# Lab_6.net
KiCad netlist of a schematic drawn in EAGLE
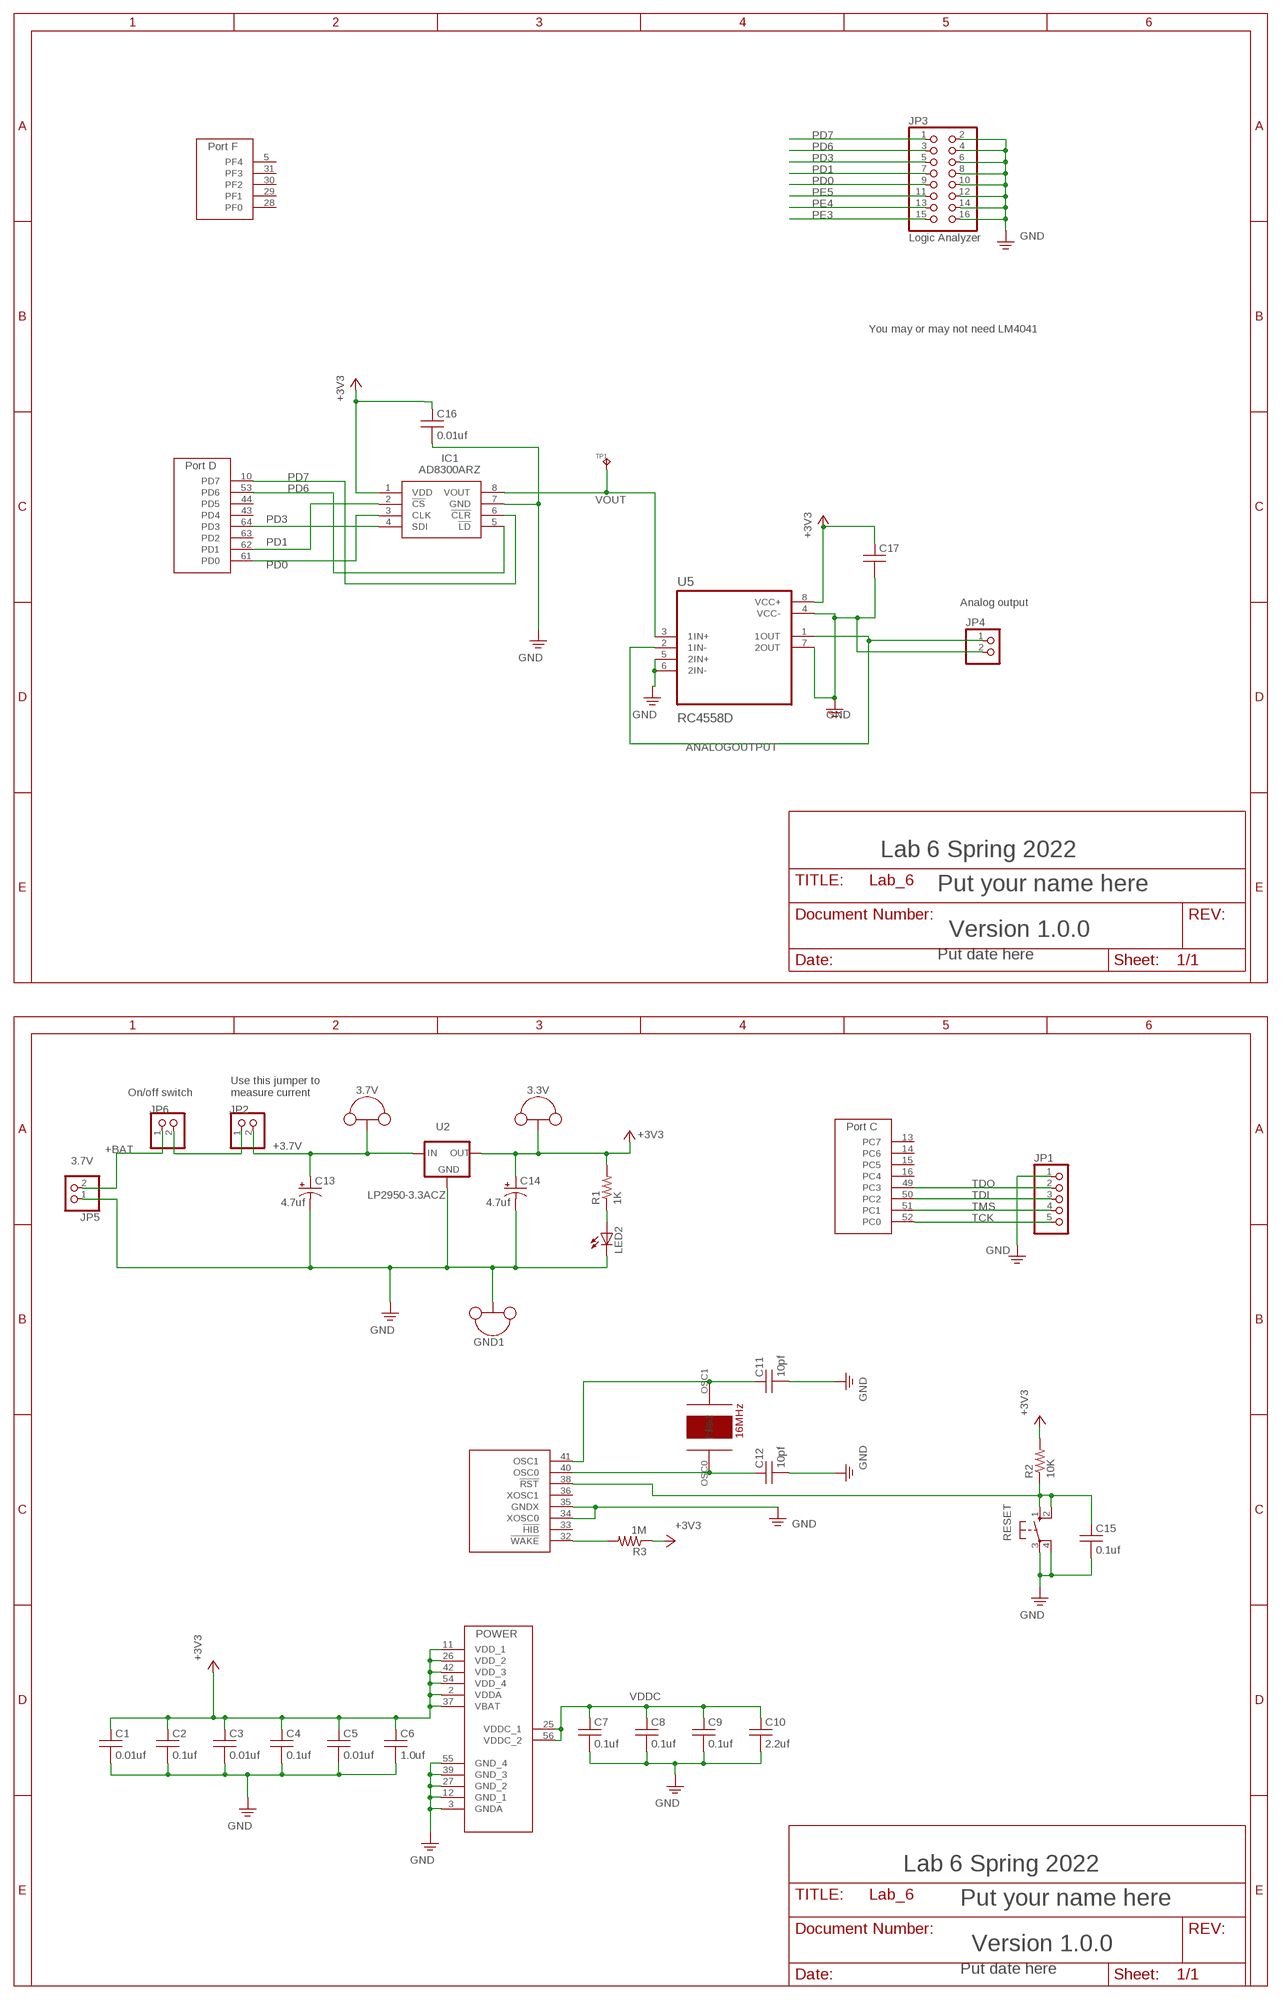
[diagram p0: schematic, sheet 1, part 1 of 2]
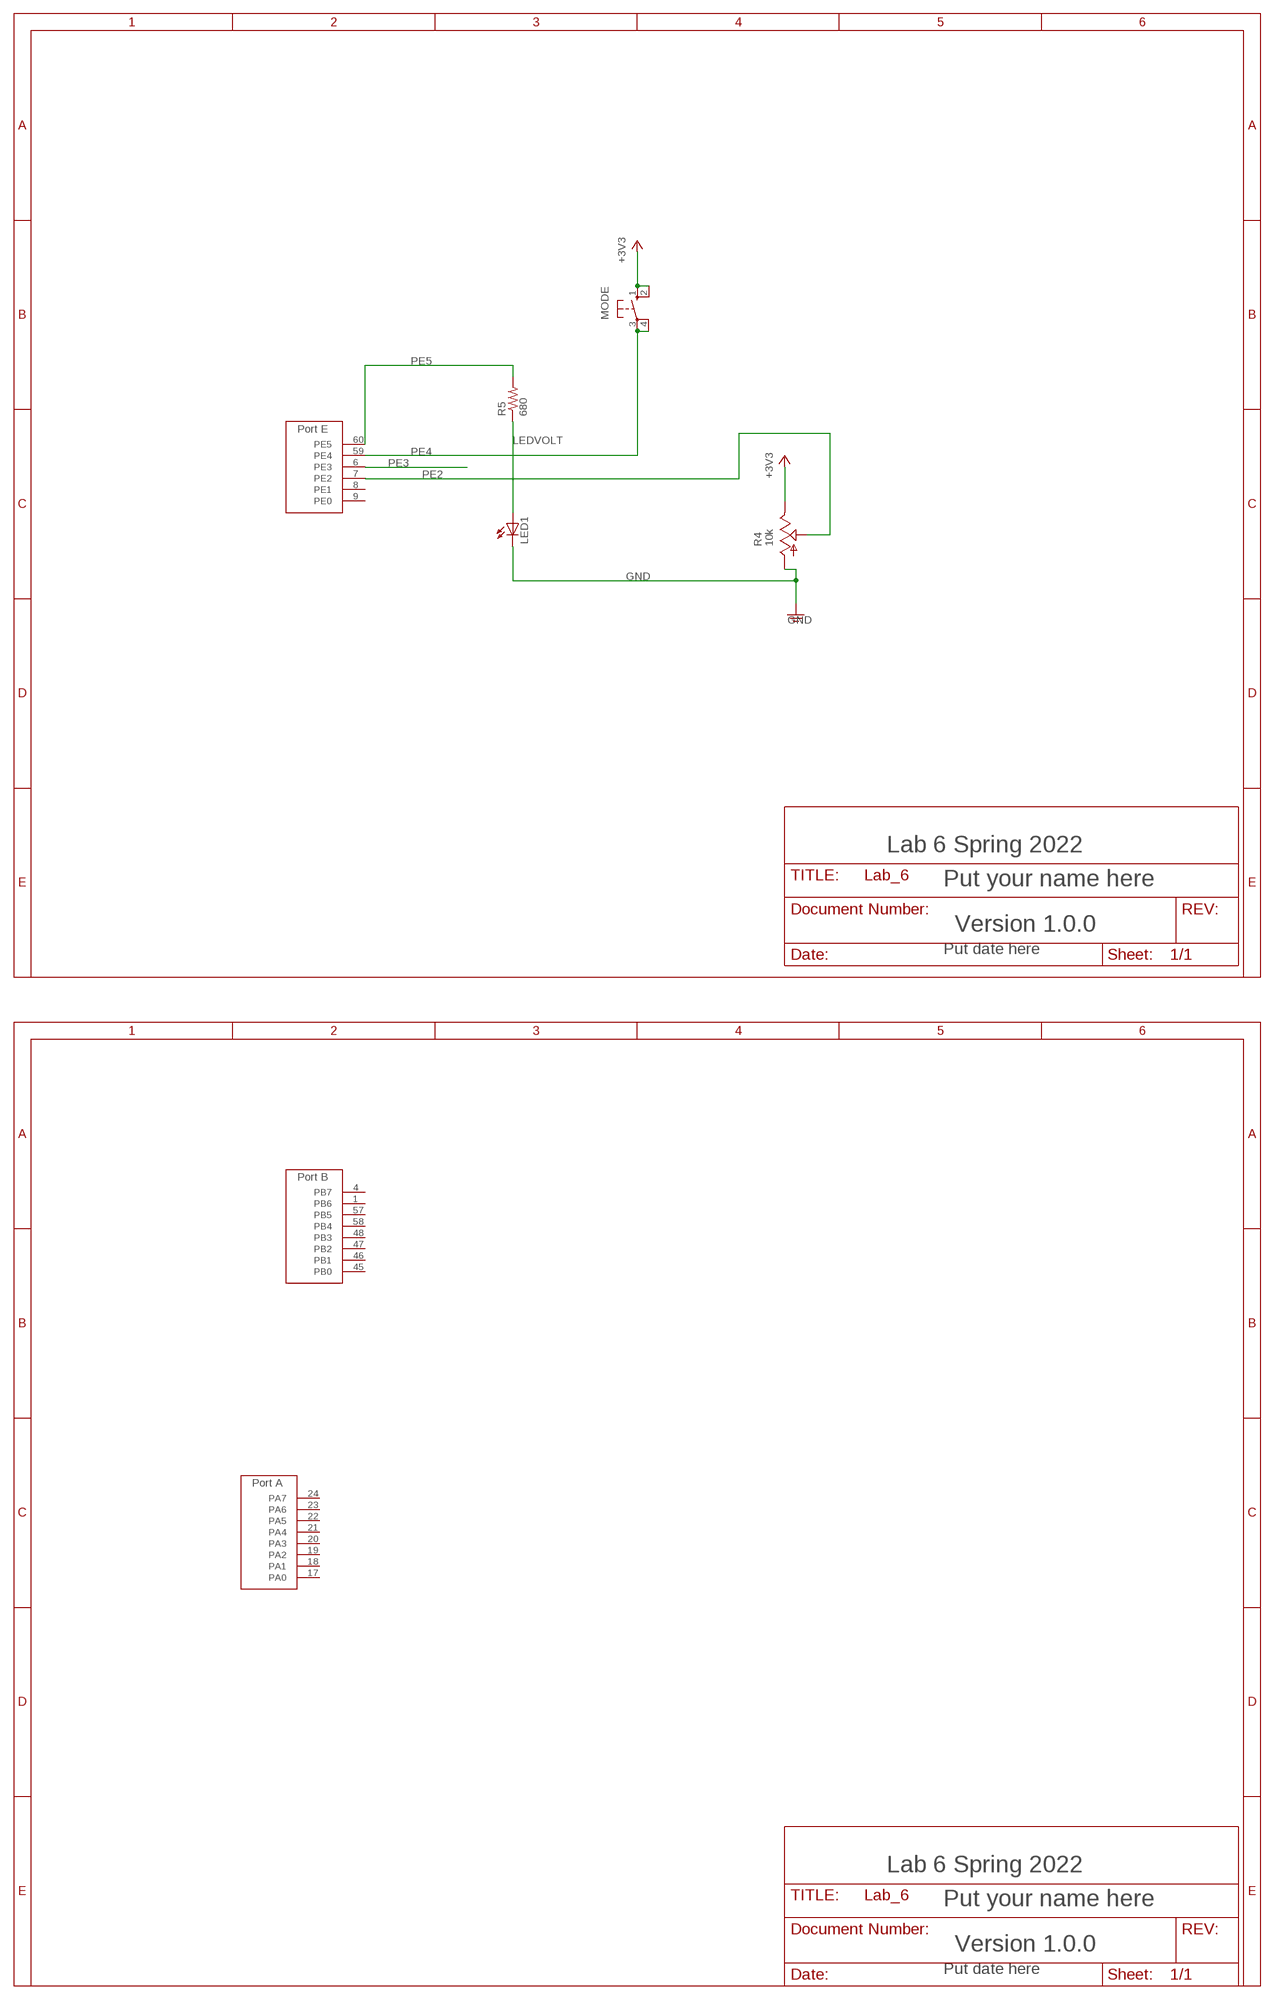
[diagram p1: schematic, sheet 1, part 2 of 2]

(export (version "E")
  (design (tool "Eeschema 10.0.6"))
  (components
    (comp (ref "3.3V")
      (value "TP_LOOP")
      (footprint "eagle-import:TP_LOOP")
      (libsource (lib "eagle-import") (part "TP_LOOP"))
    )
    (comp (ref "3.7V")
      (value "TP_LOOP")
      (footprint "eagle-import:TP_LOOP")
      (libsource (lib "eagle-import") (part "TP_LOOP"))
    )
    (comp (ref "C1")
      (value "0.01uf")
      (footprint "eagle-import:CAP100MIL")
      (libsource (lib "eagle-import") (part "CAPACITOR025-024X044"))
    )
    (comp (ref "C2")
      (value "0.1uf")
      (footprint "eagle-import:CAP100MIL")
      (libsource (lib "eagle-import") (part "CAPACITOR025-024X044"))
    )
    (comp (ref "C3")
      (value "0.01uf")
      (footprint "eagle-import:CAP100MIL")
      (libsource (lib "eagle-import") (part "CAPACITOR025-024X044"))
    )
    (comp (ref "C4")
      (value "0.1uf")
      (footprint "eagle-import:CAP100MIL")
      (libsource (lib "eagle-import") (part "CAPACITOR025-024X044"))
    )
    (comp (ref "C5")
      (value "0.01uf")
      (footprint "eagle-import:CAP100MIL")
      (libsource (lib "eagle-import") (part "CAPACITOR025-024X044"))
    )
    (comp (ref "C6")
      (value "1.0uf")
      (footprint "eagle-import:CAP100MIL")
      (libsource (lib "eagle-import") (part "CAPACITOR025-024X044"))
    )
    (comp (ref "C7")
      (value "0.1uf")
      (footprint "eagle-import:CAP100MIL")
      (libsource (lib "eagle-import") (part "CAPACITOR025-024X044"))
    )
    (comp (ref "C8")
      (value "0.1uf")
      (footprint "eagle-import:CAP100MIL")
      (libsource (lib "eagle-import") (part "CAPACITOR025-024X044"))
    )
    (comp (ref "C9")
      (value "0.1uf")
      (footprint "eagle-import:CAP100MIL")
      (libsource (lib "eagle-import") (part "CAPACITOR025-024X044"))
    )
    (comp (ref "C10")
      (value "2.2uf")
      (footprint "eagle-import:CAP100MIL")
      (libsource (lib "eagle-import") (part "CAPACITOR025-024X044"))
    )
    (comp (ref "C11")
      (value "10pf")
      (footprint "eagle-import:CAP100MIL")
      (libsource (lib "eagle-import") (part "CAPACITOR025-024X044"))
    )
    (comp (ref "C12")
      (value "10pf")
      (footprint "eagle-import:CAP100MIL")
      (libsource (lib "eagle-import") (part "CAPACITOR025-024X044"))
    )
    (comp (ref "C13")
      (value "4.7uf")
      (footprint "eagle-import:CAP200MILPOLARIZED")
      (libsource (lib "eagle-import") (part "CAPACITOR_POLARIZEDE5-6"))
    )
    (comp (ref "C14")
      (value "4.7uf")
      (footprint "eagle-import:CAP200MILPOLARIZED")
      (libsource (lib "eagle-import") (part "CAPACITOR_POLARIZEDE5-6"))
    )
    (comp (ref "C15")
      (value "0.1uf")
      (footprint "eagle-import:CAP100MIL")
      (libsource (lib "eagle-import") (part "CAPACITOR025-024X044"))
    )
    (comp (ref "C16")
      (value "0.01uf")
      (footprint "eagle-import:CAP100MIL")
      (libsource (lib "eagle-import") (part "CAPACITOR025-024X044"))
    )
    (comp (ref "C17")
      (value "0.01uf")
      (footprint "eagle-import:CAP100MIL")
      (libsource (lib "eagle-import") (part "CAPACITOR025-024X044"))
    )
    (comp (ref "GND1")
      (value "TP_LOOP")
      (footprint "eagle-import:TP_LOOP")
      (libsource (lib "eagle-import") (part "TP_LOOP"))
    )
    (comp (ref "IC1")
      (value "AD8300ARZ")
      (footprint "eagle-import:SOIC127P600X175-8N")
      (libsource (lib "eagle-import") (part "AD8300ARZ"))
    )
    (comp (ref "JP1")
      (value "PINHD-1X5")
      (footprint "eagle-import:1X05")
      (libsource (lib "eagle-import") (part "PINHD-1X5"))
    )
    (comp (ref "JP2")
      (value "PINHD-1X2")
      (footprint "eagle-import:1X02")
      (libsource (lib "eagle-import") (part "PINHD-1X2"))
    )
    (comp (ref "JP3")
      (value "Logic Analyzer")
      (footprint "eagle-import:2X08")
      (libsource (lib "eagle-import") (part "PINHD-2X8"))
    )
    (comp (ref "JP4")
      (value "PINHD-1X2")
      (footprint "eagle-import:1X02")
      (libsource (lib "eagle-import") (part "PINHD-1X2"))
    )
    (comp (ref "JP5")
      (value "PINHD-1X2")
      (footprint "eagle-import:1X02")
      (libsource (lib "eagle-import") (part "PINHD-1X2"))
    )
    (comp (ref "JP6")
      (value "PINHD-1X2")
      (footprint "eagle-import:1X02")
      (libsource (lib "eagle-import") (part "PINHD-1X2"))
    )
    (comp (ref "LED1")
      (value "LED3MM")
      (footprint "eagle-import:LED3MM")
      (libsource (lib "eagle-import") (part "LED3MM"))
    )
    (comp (ref "LED2")
      (value "LED3MM")
      (footprint "eagle-import:LED3MM")
      (libsource (lib "eagle-import") (part "LED3MM"))
    )
    (comp (ref "MODE")
      (value "B3F-1052")
      (footprint "eagle-import:B3F-10XX")
      (fields (field (name "MPN") "B3F-1000"))
      (libsource (lib "eagle-import") (part "B3F-1052"))
    )
    (comp (ref "R1")
      (value "1K")
      (footprint "eagle-import:RES200MIL")
      (libsource (lib "eagle-import") (part "RESISTOR0204/5"))
    )
    (comp (ref "R2")
      (value "10K")
      (footprint "eagle-import:RES200MIL")
      (libsource (lib "eagle-import") (part "RESISTOR0204/5"))
    )
    (comp (ref "R3")
      (value "1M")
      (footprint "eagle-import:RES200MIL")
      (libsource (lib "eagle-import") (part "RESISTOR0204/5"))
    )
    (comp (ref "R4")
      (value "10k")
      (footprint "eagle-import:PTA2043")
      (libsource (lib "eagle-import") (part "POTENTIOMETER_PTA2043B25U"))
    )
    (comp (ref "R5")
      (value "680")
      (footprint "eagle-import:RES200MIL")
      (libsource (lib "eagle-import") (part "RESISTOR0204/5"))
    )
    (comp (ref "RESET")
      (value "B3F-1052")
      (footprint "eagle-import:B3F-10XX")
      (fields (field (name "MPN") "B3F-1000"))
      (libsource (lib "eagle-import") (part "B3F-1052"))
    )
    (comp (ref "TP1")
      (value "TP_KEYSTONE500X")
      (footprint "eagle-import:P1.1MM")
      (libsource (lib "eagle-import") (part "TP_KEYSTONE500X"))
    )
    (comp (ref "U1")
      (value "TM4C123GH6PM")
      (footprint "eagle-import:QFP50P1200X1200X160-64N")
      (libsource (lib "eagle-import") (part "TM4C123GH6PM"))
    )
    (comp (ref "U2")
      (value "LP2950-3.3ACZ")
      (footprint "eagle-import:TO92")
      (libsource (lib "eagle-import") (part "LP2950ACZ-3.3"))
    )
    (comp (ref "U5")
      (value "RC4558D")
      (footprint "eagle-import:SOIC127P599X175-8N")
      (fields (field (name "MF") "Texas Instruments"))
      (libsource (lib "eagle-import") (part "RC4558D"))
    )
    (comp (ref "Y1")
      (value "16MHZ_CRYSTAL")
      (footprint "eagle-import:16MHZ_CRYSTAL")
      (libsource (lib "eagle-import") (part "16MHZ_CRYSTAL"))
    )
  )
  (nets
    (net (code "1") (name "+3V3") (class "Default")
      (node (ref "3.3V") (pin "P$1") (pinfunction "TP_P$1") (pintype "bidirectional"))
      (node (ref "3.3V") (pin "P$2") (pinfunction "TP_P$2") (pintype "bidirectional"))
      (node (ref "C1") (pin "1") (pinfunction "1_1") (pintype "passive"))
      (node (ref "C14") (pin "+") (pinfunction "+_+") (pintype "passive"))
      (node (ref "C16") (pin "1") (pinfunction "1_1") (pintype "passive"))
      (node (ref "C17") (pin "1") (pinfunction "1_1") (pintype "passive"))
      (node (ref "C2") (pin "1") (pinfunction "1_1") (pintype "passive"))
      (node (ref "C3") (pin "1") (pinfunction "1_1") (pintype "passive"))
      (node (ref "C4") (pin "1") (pinfunction "1_1") (pintype "passive"))
      (node (ref "C5") (pin "1") (pinfunction "1_1") (pintype "passive"))
      (node (ref "C6") (pin "1") (pinfunction "1_1") (pintype "passive"))
      (node (ref "IC1") (pin "1") (pinfunction "VDD_1") (pintype "bidirectional"))
      (node (ref "MODE") (pin "1") (pinfunction "S_1") (pintype "passive"))
      (node (ref "MODE") (pin "2") (pinfunction "S1_2") (pintype "passive"))
      (node (ref "R1") (pin "2") (pinfunction "2_2") (pintype "passive"))
      (node (ref "R2") (pin "2") (pinfunction "2_2") (pintype "passive"))
      (node (ref "R3") (pin "1") (pinfunction "1_1") (pintype "passive"))
      (node (ref "R4") (pin "1") (pinfunction "E_1") (pintype "passive"))
      (node (ref "U1") (pin "11") (pinfunction "VDD_1_11") (pintype "bidirectional"))
      (node (ref "U1") (pin "2") (pinfunction "VDDA_2") (pintype "bidirectional"))
      (node (ref "U1") (pin "26") (pinfunction "VDD_2_26") (pintype "bidirectional"))
      (node (ref "U1") (pin "37") (pinfunction "VBAT_37") (pintype "bidirectional"))
      (node (ref "U1") (pin "42") (pinfunction "VDD_3_42") (pintype "bidirectional"))
      (node (ref "U1") (pin "54") (pinfunction "VDD_4_54") (pintype "bidirectional"))
      (node (ref "U2") (pin "1") (pinfunction "OUT_1") (pintype "passive"))
      (node (ref "U5") (pin "8") (pinfunction "VCC+_8") (pintype "power_in"))
    )
    (net (code "2") (name "/+3.7V") (class "Default")
      (node (ref "3.7V") (pin "P$1") (pinfunction "TP_P$1") (pintype "bidirectional"))
      (node (ref "3.7V") (pin "P$2") (pinfunction "TP_P$2") (pintype "bidirectional"))
      (node (ref "C13") (pin "+") (pinfunction "+_+") (pintype "passive"))
      (node (ref "JP2") (pin "2") (pinfunction "2_2") (pintype "passive"))
      (node (ref "U2") (pin "3") (pinfunction "IN_3") (pintype "input"))
    )
    (net (code "3") (name "/+BAT") (class "Default")
      (node (ref "JP5") (pin "2") (pinfunction "2_2") (pintype "passive"))
      (node (ref "JP6") (pin "1") (pinfunction "1_1") (pintype "passive"))
    )
    (net (code "4") (name "/ANALOGOUTPUT") (class "Default")
      (node (ref "JP4") (pin "1") (pinfunction "1_1") (pintype "passive"))
      (node (ref "U5") (pin "1") (pinfunction "1OUT_1") (pintype "output"))
      (node (ref "U5") (pin "2") (pinfunction "1IN-_2") (pintype "input"))
    )
    (net (code "5") (name "/LEDVOLT") (class "Default")
      (node (ref "LED1") (pin "A") (pinfunction "A_A") (pintype "passive"))
      (node (ref "R5") (pin "1") (pinfunction "1_1") (pintype "passive"))
    )
    (net (code "6") (name "/PD0") (class "Default")
      (node (ref "IC1") (pin "3") (pinfunction "CLK_3") (pintype "bidirectional"))
      (node (ref "JP3") (pin "9") (pinfunction "9_9") (pintype "passive"))
      (node (ref "U1") (pin "61") (pinfunction "PD0_61") (pintype "bidirectional"))
    )
    (net (code "7") (name "/PD1") (class "Default")
      (node (ref "IC1") (pin "2") (pinfunction "~{CS}_2") (pintype "bidirectional"))
      (node (ref "JP3") (pin "7") (pinfunction "7_7") (pintype "passive"))
      (node (ref "U1") (pin "62") (pinfunction "PD1_62") (pintype "bidirectional"))
    )
    (net (code "8") (name "/PD3") (class "Default")
      (node (ref "IC1") (pin "4") (pinfunction "SDI_4") (pintype "bidirectional"))
      (node (ref "JP3") (pin "5") (pinfunction "5_5") (pintype "passive"))
      (node (ref "U1") (pin "64") (pinfunction "PD3_64") (pintype "bidirectional"))
    )
    (net (code "9") (name "/PD6") (class "Default")
      (node (ref "IC1") (pin "5") (pinfunction "~{LD}_5") (pintype "bidirectional"))
      (node (ref "JP3") (pin "3") (pinfunction "3_3") (pintype "passive"))
      (node (ref "U1") (pin "53") (pinfunction "PD6_53") (pintype "bidirectional"))
    )
    (net (code "10") (name "/PD7") (class "Default")
      (node (ref "IC1") (pin "6") (pinfunction "~{CLR}_6") (pintype "bidirectional"))
      (node (ref "JP3") (pin "1") (pinfunction "1_1") (pintype "passive"))
      (node (ref "U1") (pin "10") (pinfunction "PD7_10") (pintype "bidirectional"))
    )
    (net (code "11") (name "/PE2") (class "Default")
      (node (ref "R4") (pin "2") (pinfunction "S_2") (pintype "passive"))
      (node (ref "U1") (pin "7") (pinfunction "PE2_7") (pintype "bidirectional"))
    )
    (net (code "12") (name "/PE3") (class "Default")
      (node (ref "JP3") (pin "15") (pinfunction "15_15") (pintype "passive"))
      (node (ref "U1") (pin "6") (pinfunction "PE3_6") (pintype "bidirectional"))
    )
    (net (code "13") (name "/PE4") (class "Default")
      (node (ref "JP3") (pin "13") (pinfunction "13_13") (pintype "passive"))
      (node (ref "MODE") (pin "3") (pinfunction "P_3") (pintype "passive"))
      (node (ref "MODE") (pin "4") (pinfunction "P1_4") (pintype "passive"))
      (node (ref "U1") (pin "59") (pinfunction "PE4_59") (pintype "bidirectional"))
    )
    (net (code "14") (name "/PE5") (class "Default")
      (node (ref "JP3") (pin "11") (pinfunction "11_11") (pintype "passive"))
      (node (ref "R5") (pin "2") (pinfunction "2_2") (pintype "passive"))
      (node (ref "U1") (pin "60") (pinfunction "PE5_60") (pintype "bidirectional"))
    )
    (net (code "15") (name "/TCK") (class "Default")
      (node (ref "JP1") (pin "5") (pinfunction "5_5") (pintype "passive"))
      (node (ref "U1") (pin "52") (pinfunction "PC0_52") (pintype "bidirectional"))
    )
    (net (code "16") (name "/TDI") (class "Default")
      (node (ref "JP1") (pin "3") (pinfunction "3_3") (pintype "passive"))
      (node (ref "U1") (pin "50") (pinfunction "PC2_50") (pintype "bidirectional"))
    )
    (net (code "17") (name "/TDO") (class "Default")
      (node (ref "JP1") (pin "2") (pinfunction "2_2") (pintype "passive"))
      (node (ref "U1") (pin "49") (pinfunction "PC3_49") (pintype "bidirectional"))
    )
    (net (code "18") (name "/TMS") (class "Default")
      (node (ref "JP1") (pin "4") (pinfunction "4_4") (pintype "passive"))
      (node (ref "U1") (pin "51") (pinfunction "PC1_51") (pintype "bidirectional"))
    )
    (net (code "19") (name "/VDDC") (class "Default")
      (node (ref "C10") (pin "1") (pinfunction "1_1") (pintype "passive"))
      (node (ref "C7") (pin "1") (pinfunction "1_1") (pintype "passive"))
      (node (ref "C8") (pin "1") (pinfunction "1_1") (pintype "passive"))
      (node (ref "C9") (pin "1") (pinfunction "1_1") (pintype "passive"))
      (node (ref "U1") (pin "25") (pinfunction "VDDC_1_25") (pintype "bidirectional"))
      (node (ref "U1") (pin "56") (pinfunction "VDDC_2_56") (pintype "bidirectional"))
    )
    (net (code "20") (name "/VOUT") (class "Default")
      (node (ref "IC1") (pin "8") (pinfunction "VOUT_8") (pintype "bidirectional"))
      (node (ref "TP1") (pin "TP") (pinfunction "TP_TP") (pintype "input"))
      (node (ref "U5") (pin "3") (pinfunction "1IN+_3") (pintype "input"))
    )
    (net (code "21") (name "GND") (class "Default")
      (node (ref "C1") (pin "2") (pinfunction "2_2") (pintype "passive"))
      (node (ref "C10") (pin "2") (pinfunction "2_2") (pintype "passive"))
      (node (ref "C11") (pin "2") (pinfunction "2_2") (pintype "passive"))
      (node (ref "C12") (pin "2") (pinfunction "2_2") (pintype "passive"))
      (node (ref "C13") (pin "-") (pinfunction "-_-") (pintype "passive"))
      (node (ref "C14") (pin "-") (pinfunction "-_-") (pintype "passive"))
      (node (ref "C15") (pin "2") (pinfunction "2_2") (pintype "passive"))
      (node (ref "C16") (pin "2") (pinfunction "2_2") (pintype "passive"))
      (node (ref "C17") (pin "2") (pinfunction "2_2") (pintype "passive"))
      (node (ref "C2") (pin "2") (pinfunction "2_2") (pintype "passive"))
      (node (ref "C3") (pin "2") (pinfunction "2_2") (pintype "passive"))
      (node (ref "C4") (pin "2") (pinfunction "2_2") (pintype "passive"))
      (node (ref "C5") (pin "2") (pinfunction "2_2") (pintype "passive"))
      (node (ref "C6") (pin "2") (pinfunction "2_2") (pintype "passive"))
      (node (ref "C7") (pin "2") (pinfunction "2_2") (pintype "passive"))
      (node (ref "C8") (pin "2") (pinfunction "2_2") (pintype "passive"))
      (node (ref "C9") (pin "2") (pinfunction "2_2") (pintype "passive"))
      (node (ref "GND1") (pin "P$1") (pinfunction "TP_P$1") (pintype "bidirectional"))
      (node (ref "GND1") (pin "P$2") (pinfunction "TP_P$2") (pintype "bidirectional"))
      (node (ref "IC1") (pin "7") (pinfunction "GND_7") (pintype "bidirectional"))
      (node (ref "JP1") (pin "1") (pinfunction "1_1") (pintype "passive"))
      (node (ref "JP3") (pin "10") (pinfunction "10_10") (pintype "passive"))
      (node (ref "JP3") (pin "12") (pinfunction "12_12") (pintype "passive"))
      (node (ref "JP3") (pin "14") (pinfunction "14_14") (pintype "passive"))
      (node (ref "JP3") (pin "16") (pinfunction "16_16") (pintype "passive"))
      (node (ref "JP3") (pin "2") (pinfunction "2_2") (pintype "passive"))
      (node (ref "JP3") (pin "4") (pinfunction "4_4") (pintype "passive"))
      (node (ref "JP3") (pin "6") (pinfunction "6_6") (pintype "passive"))
      (node (ref "JP3") (pin "8") (pinfunction "8_8") (pintype "passive"))
      (node (ref "JP4") (pin "2") (pinfunction "2_2") (pintype "passive"))
      (node (ref "JP5") (pin "1") (pinfunction "1_1") (pintype "passive"))
      (node (ref "LED1") (pin "K") (pinfunction "C_K") (pintype "passive"))
      (node (ref "LED2") (pin "K") (pinfunction "C_K") (pintype "passive"))
      (node (ref "R4") (pin "3") (pinfunction "A_3") (pintype "passive"))
      (node (ref "RESET") (pin "3") (pinfunction "P_3") (pintype "passive"))
      (node (ref "RESET") (pin "4") (pinfunction "P1_4") (pintype "passive"))
      (node (ref "U1") (pin "12") (pinfunction "GND_1_12") (pintype "bidirectional"))
      (node (ref "U1") (pin "27") (pinfunction "GND_2_27") (pintype "bidirectional"))
      (node (ref "U1") (pin "3") (pinfunction "GNDA_3") (pintype "bidirectional"))
      (node (ref "U1") (pin "34") (pinfunction "XOSC0_34") (pintype "bidirectional"))
      (node (ref "U1") (pin "35") (pinfunction "GNDX_35") (pintype "bidirectional"))
      (node (ref "U1") (pin "39") (pinfunction "GND_3_39") (pintype "bidirectional"))
      (node (ref "U1") (pin "55") (pinfunction "GND_4_55") (pintype "bidirectional"))
      (node (ref "U2") (pin "2") (pinfunction "GND_2") (pintype "input"))
      (node (ref "U5") (pin "4") (pinfunction "VCC-_4") (pintype "power_in"))
      (node (ref "U5") (pin "5") (pinfunction "2IN+_5") (pintype "input"))
      (node (ref "U5") (pin "6") (pinfunction "2IN-_6") (pintype "input"))
      (node (ref "U5") (pin "7") (pinfunction "2OUT_7") (pintype "output"))
    )
    (net (code "22") (name "Net-(JP2-Pad1)") (class "Default")
      (node (ref "JP2") (pin "1") (pinfunction "1_1") (pintype "passive"))
      (node (ref "JP6") (pin "2") (pinfunction "2_2") (pintype "passive"))
    )
    (net (code "23") (name "Net-(LED2-PadA)") (class "Default")
      (node (ref "LED2") (pin "A") (pinfunction "A_A") (pintype "passive"))
      (node (ref "R1") (pin "1") (pinfunction "1_1") (pintype "passive"))
    )
    (net (code "24") (name "Net-(RESET-S)") (class "Default")
      (node (ref "C15") (pin "1") (pinfunction "1_1") (pintype "passive"))
      (node (ref "R2") (pin "1") (pinfunction "1_1") (pintype "passive"))
      (node (ref "RESET") (pin "1") (pinfunction "S_1") (pintype "passive"))
      (node (ref "RESET") (pin "2") (pinfunction "S1_2") (pintype "passive"))
      (node (ref "U1") (pin "38") (pinfunction "~{RST}_38") (pintype "bidirectional"))
    )
    (net (code "25") (name "Net-(U1G-OSC0)") (class "Default")
      (node (ref "C12") (pin "1") (pinfunction "1_1") (pintype "passive"))
      (node (ref "U1") (pin "40") (pinfunction "OSC0_40") (pintype "bidirectional"))
      (node (ref "Y1") (pin "OSC0") (pinfunction "P$1_OSC0") (pintype "bidirectional"))
    )
    (net (code "26") (name "Net-(U1G-OSC1)") (class "Default")
      (node (ref "C11") (pin "1") (pinfunction "1_1") (pintype "passive"))
      (node (ref "U1") (pin "41") (pinfunction "OSC1_41") (pintype "bidirectional"))
      (node (ref "Y1") (pin "OSC1") (pinfunction "P$2_OSC1") (pintype "bidirectional"))
    )
    (net (code "27") (name "Net-(U1G-~{WAKE})") (class "Default")
      (node (ref "R3") (pin "2") (pinfunction "2_2") (pintype "passive"))
      (node (ref "U1") (pin "32") (pinfunction "~{WAKE}_32") (pintype "bidirectional"))
    )
    (net (code "28") (name "unconnected-(U1A-PA0-Pad17)") (class "Default")
      (node (ref "U1") (pin "17") (pinfunction "PA0_17") (pintype "bidirectional"))
    )
    (net (code "29") (name "unconnected-(U1A-PA1-Pad18)") (class "Default")
      (node (ref "U1") (pin "18") (pinfunction "PA1_18") (pintype "bidirectional"))
    )
    (net (code "30") (name "unconnected-(U1A-PA2-Pad19)") (class "Default")
      (node (ref "U1") (pin "19") (pinfunction "PA2_19") (pintype "bidirectional"))
    )
    (net (code "31") (name "unconnected-(U1A-PA3-Pad20)") (class "Default")
      (node (ref "U1") (pin "20") (pinfunction "PA3_20") (pintype "bidirectional"))
    )
    (net (code "32") (name "unconnected-(U1A-PA4-Pad21)") (class "Default")
      (node (ref "U1") (pin "21") (pinfunction "PA4_21") (pintype "bidirectional"))
    )
    (net (code "33") (name "unconnected-(U1A-PA5-Pad22)") (class "Default")
      (node (ref "U1") (pin "22") (pinfunction "PA5_22") (pintype "bidirectional"))
    )
    (net (code "34") (name "unconnected-(U1A-PA6-Pad23)") (class "Default")
      (node (ref "U1") (pin "23") (pinfunction "PA6_23") (pintype "bidirectional"))
    )
    (net (code "35") (name "unconnected-(U1A-PA7-Pad24)") (class "Default")
      (node (ref "U1") (pin "24") (pinfunction "PA7_24") (pintype "bidirectional"))
    )
    (net (code "36") (name "unconnected-(U1B-PB0-Pad45)") (class "Default")
      (node (ref "U1") (pin "45") (pinfunction "PB0_45") (pintype "bidirectional"))
    )
    (net (code "37") (name "unconnected-(U1B-PB1-Pad46)") (class "Default")
      (node (ref "U1") (pin "46") (pinfunction "PB1_46") (pintype "bidirectional"))
    )
    (net (code "38") (name "unconnected-(U1B-PB2-Pad47)") (class "Default")
      (node (ref "U1") (pin "47") (pinfunction "PB2_47") (pintype "bidirectional"))
    )
    (net (code "39") (name "unconnected-(U1B-PB3-Pad48)") (class "Default")
      (node (ref "U1") (pin "48") (pinfunction "PB3_48") (pintype "bidirectional"))
    )
    (net (code "40") (name "unconnected-(U1B-PB4-Pad58)") (class "Default")
      (node (ref "U1") (pin "58") (pinfunction "PB4_58") (pintype "bidirectional"))
    )
    (net (code "41") (name "unconnected-(U1B-PB5-Pad57)") (class "Default")
      (node (ref "U1") (pin "57") (pinfunction "PB5_57") (pintype "bidirectional"))
    )
    (net (code "42") (name "unconnected-(U1B-PB6-Pad1)") (class "Default")
      (node (ref "U1") (pin "1") (pinfunction "PB6_1") (pintype "bidirectional"))
    )
    (net (code "43") (name "unconnected-(U1B-PB7-Pad4)") (class "Default")
      (node (ref "U1") (pin "4") (pinfunction "PB7_4") (pintype "bidirectional"))
    )
    (net (code "44") (name "unconnected-(U1C-PC4-Pad16)") (class "Default")
      (node (ref "U1") (pin "16") (pinfunction "PC4_16") (pintype "bidirectional"))
    )
    (net (code "45") (name "unconnected-(U1C-PC5-Pad15)") (class "Default")
      (node (ref "U1") (pin "15") (pinfunction "PC5_15") (pintype "bidirectional"))
    )
    (net (code "46") (name "unconnected-(U1C-PC6-Pad14)") (class "Default")
      (node (ref "U1") (pin "14") (pinfunction "PC6_14") (pintype "bidirectional"))
    )
    (net (code "47") (name "unconnected-(U1C-PC7-Pad13)") (class "Default")
      (node (ref "U1") (pin "13") (pinfunction "PC7_13") (pintype "bidirectional"))
    )
    (net (code "48") (name "unconnected-(U1D-PD2-Pad63)") (class "Default")
      (node (ref "U1") (pin "63") (pinfunction "PD2_63") (pintype "bidirectional"))
    )
    (net (code "49") (name "unconnected-(U1D-PD4-Pad43)") (class "Default")
      (node (ref "U1") (pin "43") (pinfunction "PD4_43") (pintype "bidirectional"))
    )
    (net (code "50") (name "unconnected-(U1D-PD5-Pad44)") (class "Default")
      (node (ref "U1") (pin "44") (pinfunction "PD5_44") (pintype "bidirectional"))
    )
    (net (code "51") (name "unconnected-(U1E-PE0-Pad9)") (class "Default")
      (node (ref "U1") (pin "9") (pinfunction "PE0_9") (pintype "bidirectional"))
    )
    (net (code "52") (name "unconnected-(U1E-PE1-Pad8)") (class "Default")
      (node (ref "U1") (pin "8") (pinfunction "PE1_8") (pintype "bidirectional"))
    )
    (net (code "53") (name "unconnected-(U1F-PF0-Pad28)") (class "Default")
      (node (ref "U1") (pin "28") (pinfunction "PF0_28") (pintype "bidirectional"))
    )
    (net (code "54") (name "unconnected-(U1F-PF1-Pad29)") (class "Default")
      (node (ref "U1") (pin "29") (pinfunction "PF1_29") (pintype "bidirectional"))
    )
    (net (code "55") (name "unconnected-(U1F-PF2-Pad30)") (class "Default")
      (node (ref "U1") (pin "30") (pinfunction "PF2_30") (pintype "bidirectional"))
    )
    (net (code "56") (name "unconnected-(U1F-PF3-Pad31)") (class "Default")
      (node (ref "U1") (pin "31") (pinfunction "PF3_31") (pintype "bidirectional"))
    )
    (net (code "57") (name "unconnected-(U1F-PF4-Pad5)") (class "Default")
      (node (ref "U1") (pin "5") (pinfunction "PF4_5") (pintype "bidirectional"))
    )
    (net (code "58") (name "unconnected-(U1G-XOSC1-Pad36)") (class "Default")
      (node (ref "U1") (pin "36") (pinfunction "XOSC1_36") (pintype "bidirectional"))
    )
    (net (code "59") (name "unconnected-(U1G-~{HIB}-Pad33)") (class "Default")
      (node (ref "U1") (pin "33") (pinfunction "~{HIB}_33") (pintype "bidirectional"))
    )
  )
)
